# 180V_power.net
KiCad netlist of a schematic drawn in EAGLE
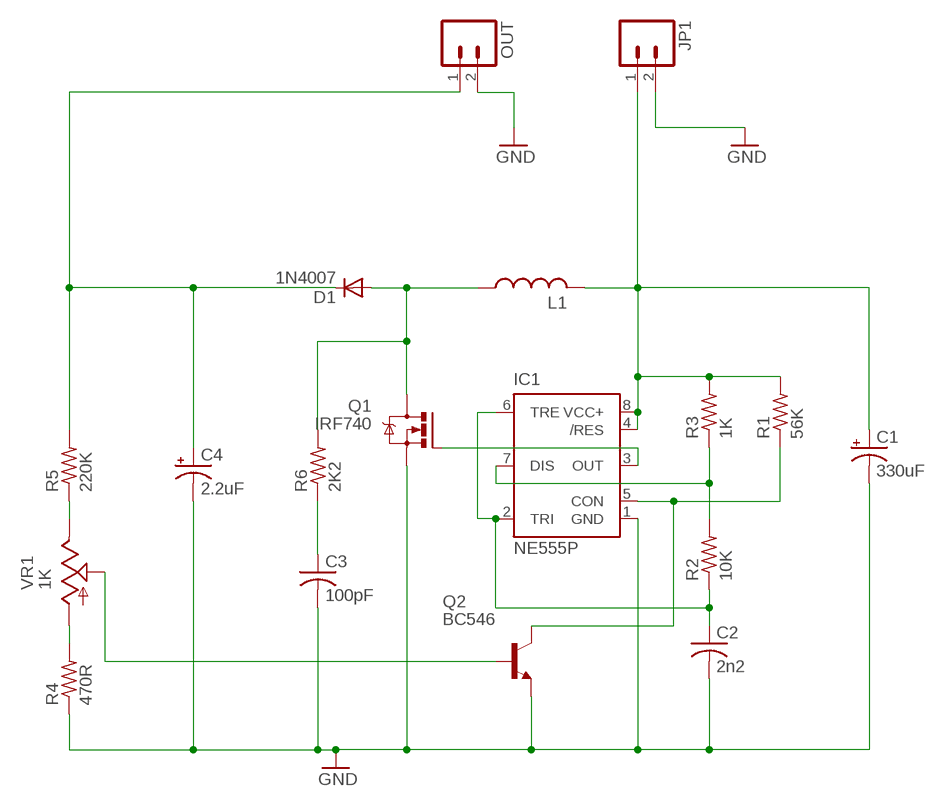
[diagram p0: schematic, sheet 1]

(export (version "E")
  (design (tool "Eeschema 10.0.6"))
  (components
    (comp (ref "C1")
      (value "330uF")
      (footprint "eagle-import:E5-10,5")
      (libsource (lib "eagle-import") (part "CAPACITOR_POLE5-10.5"))
    )
    (comp (ref "C2")
      (value "2n2")
      (footprint "eagle-import:C050-025X075")
      (libsource (lib "eagle-import") (part "CAPACITOR050-025X075"))
    )
    (comp (ref "C3")
      (value "100pF")
      (footprint "eagle-import:C050-025X075")
      (libsource (lib "eagle-import") (part "CAPACITOR050-025X075"))
    )
    (comp (ref "C4")
      (value "2.2uF")
      (footprint "eagle-import:E3,5-8")
      (libsource (lib "eagle-import") (part "CAPACITOR_POLE3.5-8"))
    )
    (comp (ref "D1")
      (value "1N4007")
      (footprint "eagle-import:DIODE-1N4001")
      (libsource (lib "eagle-import") (part "DIODEPTH"))
    )
    (comp (ref "IC1")
      (value "NE555P")
      (footprint "eagle-import:DIL08")
      (fields (field (name "MF") "Arrow Electronics") (field (name "MPN") "NE555N"))
      (libsource (lib "eagle-import") (part "NE555P"))
    )
    (comp (ref "JP1")
      (value "M023.5MM")
      (footprint "eagle-import:SCREWTERMINAL-3.5MM-2")
      (libsource (lib "eagle-import") (part "M023.5MM"))
    )
    (comp (ref "L1")
      (value "INDUCTOR")
      (footprint "eagle-import:RBL0712")
      (libsource (lib "eagle-import") (part "INDUCTOR"))
    )
    (comp (ref "OUT")
      (value "M023.5MM")
      (footprint "eagle-import:SCREWTERMINAL-3.5MM-2")
      (libsource (lib "eagle-import") (part "M023.5MM"))
    )
    (comp (ref "Q1")
      (value "IRF740")
      (footprint "eagle-import:TO220BV")
      (libsource (lib "eagle-import") (part "IRF740"))
    )
    (comp (ref "Q2")
      (value "BC546")
      (footprint "eagle-import:TO92-EBC")
      (libsource (lib "eagle-import") (part "BC546A"))
    )
    (comp (ref "R1")
      (value "56K")
      (footprint "eagle-import:0207_10")
      (libsource (lib "eagle-import") (part "RESISTOR0207/10"))
    )
    (comp (ref "R2")
      (value "10K")
      (footprint "eagle-import:0207_10")
      (libsource (lib "eagle-import") (part "RESISTOR0207/10"))
    )
    (comp (ref "R3")
      (value "1K")
      (footprint "eagle-import:0207_10")
      (libsource (lib "eagle-import") (part "RESISTOR0207/10"))
    )
    (comp (ref "R4")
      (value "470R")
      (footprint "eagle-import:0207_10")
      (libsource (lib "eagle-import") (part "RESISTOR0207/10"))
    )
    (comp (ref "R5")
      (value "220K")
      (footprint "eagle-import:0207_10")
      (libsource (lib "eagle-import") (part "RESISTOR0207/10"))
    )
    (comp (ref "R6")
      (value "2K2")
      (footprint "eagle-import:0207_10")
      (libsource (lib "eagle-import") (part "RESISTOR0207/10"))
    )
    (comp (ref "VR1")
      (value "1K")
      (footprint "eagle-import:CA6V")
      (libsource (lib "eagle-import") (part "TRIM_POTCA6V"))
    )
  )
  (nets
    (net (code "1") (name "GND") (class "Default")
      (node (ref "C1") (pin "-") (pinfunction "-_-") (pintype "passive"))
      (node (ref "C2") (pin "2") (pinfunction "2_2") (pintype "passive"))
      (node (ref "C3") (pin "2") (pinfunction "2_2") (pintype "passive"))
      (node (ref "C4") (pin "-") (pinfunction "-_-") (pintype "passive"))
      (node (ref "IC1") (pin "1") (pinfunction "GND_1") (pintype "power_in"))
      (node (ref "JP1") (pin "2") (pinfunction "2_2") (pintype "passive"))
      (node (ref "OUT") (pin "2") (pinfunction "2_2") (pintype "passive"))
      (node (ref "Q1") (pin "S") (pinfunction "S_S") (pintype "passive"))
      (node (ref "Q2") (pin "E") (pinfunction "E_E") (pintype "passive"))
      (node (ref "R4") (pin "1") (pinfunction "1_1") (pintype "passive"))
    )
    (net (code "2") (name "Net-(C3-Pad1)") (class "Default")
      (node (ref "C3") (pin "1") (pinfunction "1_1") (pintype "passive"))
      (node (ref "R6") (pin "1") (pinfunction "1_1") (pintype "passive"))
    )
    (net (code "3") (name "Net-(C4-Pad+)") (class "Default")
      (node (ref "C4") (pin "+") (pinfunction "+_+") (pintype "passive"))
      (node (ref "D1") (pin "C") (pinfunction "C_C") (pintype "passive"))
      (node (ref "OUT") (pin "1") (pinfunction "1_1") (pintype "passive"))
      (node (ref "R5") (pin "2") (pinfunction "2_2") (pintype "passive"))
    )
    (net (code "4") (name "Net-(IC1-CON)") (class "Default")
      (node (ref "IC1") (pin "5") (pinfunction "CON_5") (pintype "input"))
      (node (ref "Q2") (pin "C") (pinfunction "C_C") (pintype "passive"))
      (node (ref "R1") (pin "1") (pinfunction "1_1") (pintype "passive"))
    )
    (net (code "5") (name "Net-(IC1-DIS)") (class "Default")
      (node (ref "IC1") (pin "7") (pinfunction "DIS_7") (pintype "input"))
      (node (ref "R2") (pin "2") (pinfunction "2_2") (pintype "passive"))
      (node (ref "R3") (pin "1") (pinfunction "1_1") (pintype "passive"))
    )
    (net (code "6") (name "Net-(IC1-OUT)") (class "Default")
      (node (ref "IC1") (pin "3") (pinfunction "OUT_3") (pintype "output"))
      (node (ref "Q1") (pin "G") (pinfunction "G_G") (pintype "passive"))
    )
    (net (code "7") (name "Net-(IC1-TRE)") (class "Default")
      (node (ref "C2") (pin "1") (pinfunction "1_1") (pintype "passive"))
      (node (ref "IC1") (pin "2") (pinfunction "TRI_2") (pintype "input"))
      (node (ref "IC1") (pin "6") (pinfunction "TRE_6") (pintype "input"))
      (node (ref "R2") (pin "1") (pinfunction "1_1") (pintype "passive"))
    )
    (net (code "8") (name "Net-(IC1-VCC+)") (class "Default")
      (node (ref "C1") (pin "+") (pinfunction "+_+") (pintype "passive"))
      (node (ref "IC1") (pin "4") (pinfunction "/RES_4") (pintype "input"))
      (node (ref "IC1") (pin "8") (pinfunction "VCC+_8") (pintype "power_in"))
      (node (ref "JP1") (pin "1") (pinfunction "1_1") (pintype "passive"))
      (node (ref "L1") (pin "P$2") (pinfunction "2_P$2") (pintype "passive"))
      (node (ref "R1") (pin "2") (pinfunction "2_2") (pintype "passive"))
      (node (ref "R3") (pin "2") (pinfunction "2_2") (pintype "passive"))
    )
    (net (code "9") (name "Net-(L1-1)") (class "Default")
      (node (ref "D1") (pin "A") (pinfunction "A_A") (pintype "passive"))
      (node (ref "L1") (pin "P$1") (pinfunction "1_P$1") (pintype "passive"))
      (node (ref "Q1") (pin "D") (pinfunction "D_D") (pintype "passive"))
      (node (ref "R6") (pin "2") (pinfunction "2_2") (pintype "passive"))
    )
    (net (code "10") (name "Net-(Q2-PadB)") (class "Default")
      (node (ref "Q2") (pin "B") (pinfunction "B_B") (pintype "passive"))
      (node (ref "VR1") (pin "S") (pinfunction "S_S") (pintype "passive"))
    )
    (net (code "11") (name "Net-(R4-Pad2)") (class "Default")
      (node (ref "R4") (pin "2") (pinfunction "2_2") (pintype "passive"))
      (node (ref "VR1") (pin "A") (pinfunction "A_A") (pintype "passive"))
    )
    (net (code "12") (name "Net-(R5-Pad1)") (class "Default")
      (node (ref "R5") (pin "1") (pinfunction "1_1") (pintype "passive"))
      (node (ref "VR1") (pin "E") (pinfunction "E_E") (pintype "passive"))
    )
  )
)
